# Main_Flight_Computer.net
KiCad netlist of a schematic drawn in EAGLE
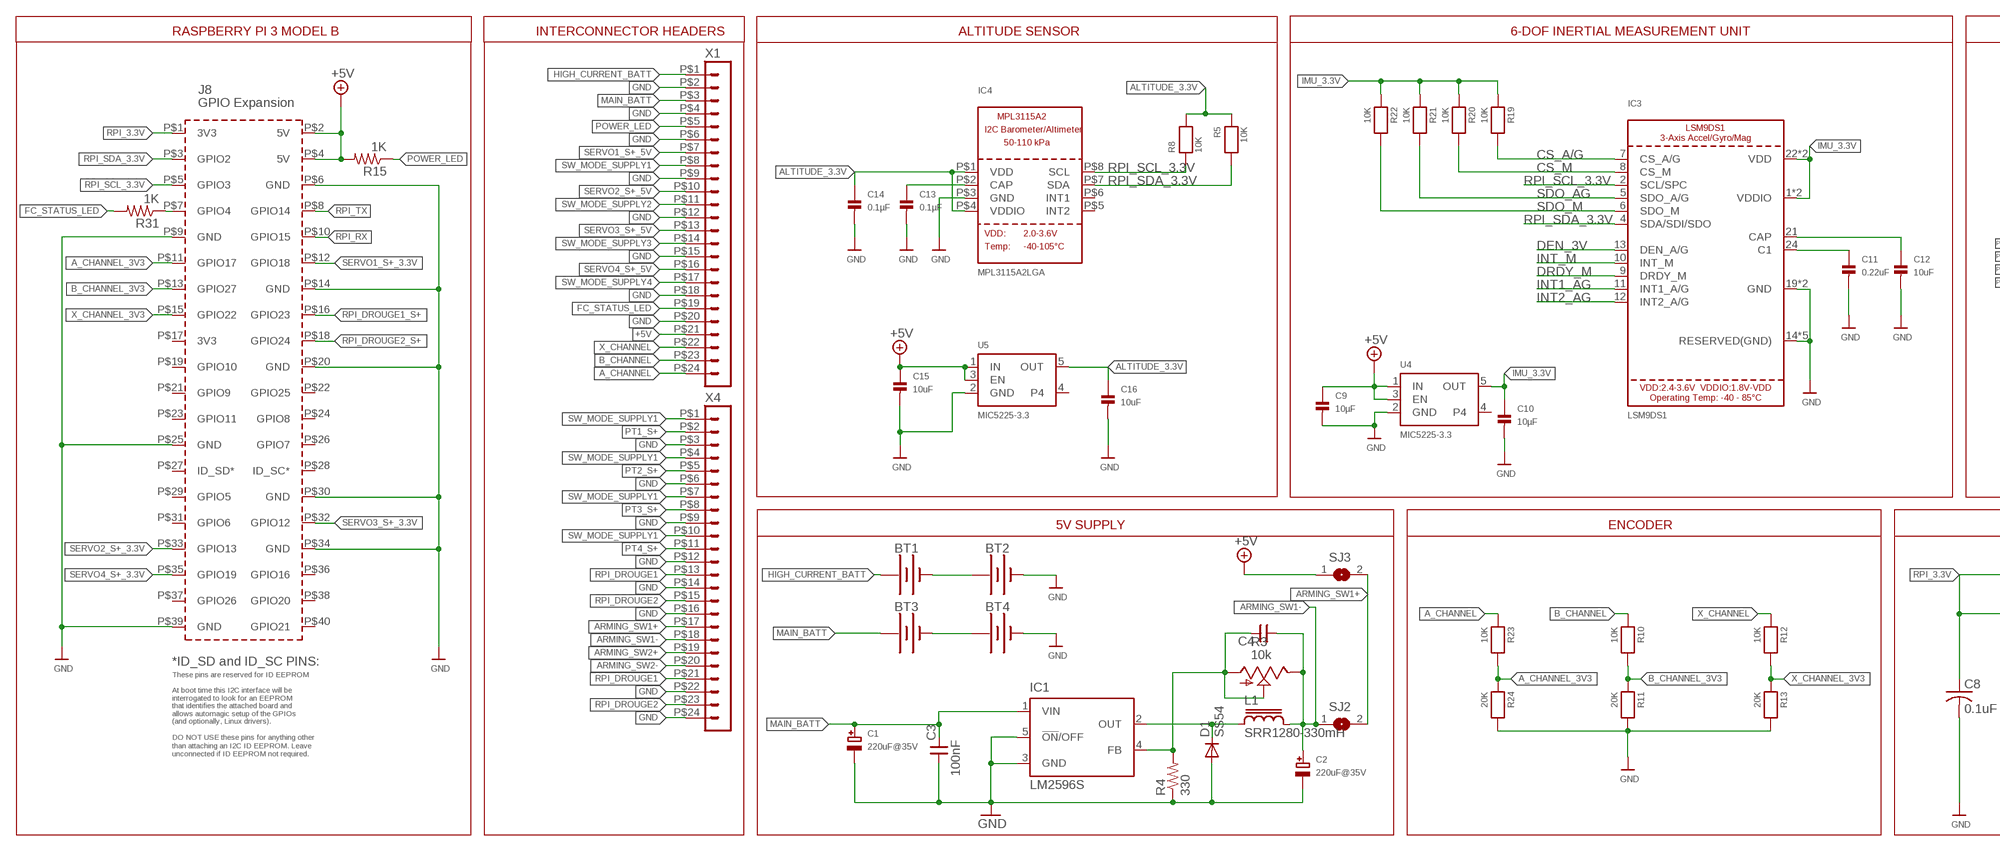
[diagram p0: schematic, sheet 1, part 1 of 2]
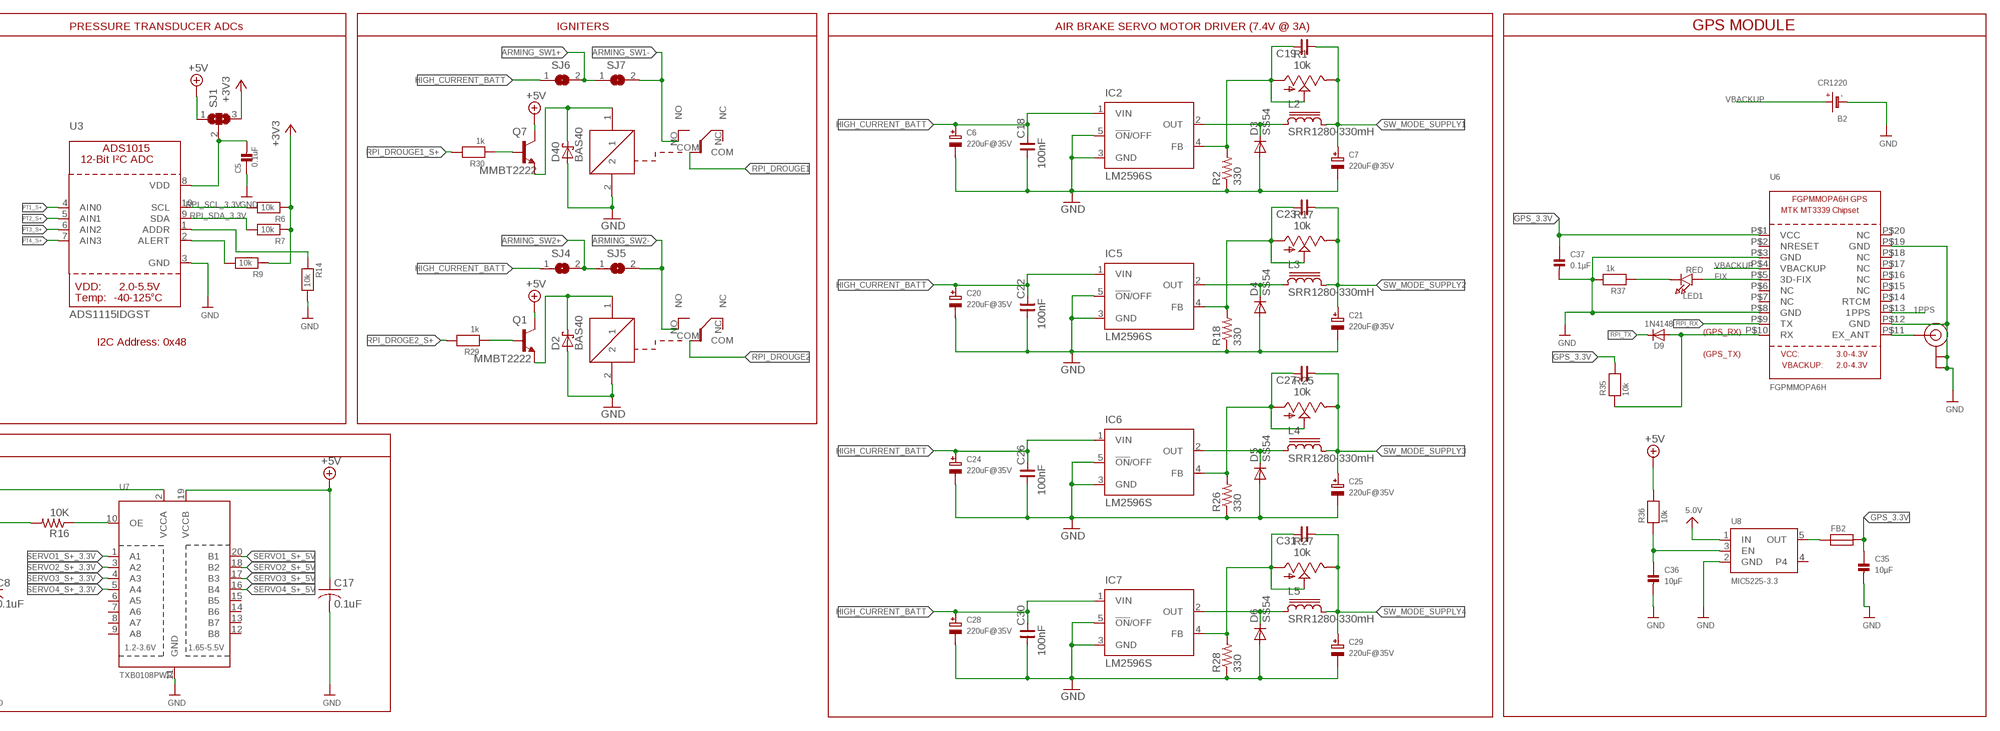
[diagram p1: schematic, sheet 1, part 2 of 2]

(export (version "E")
  (design (tool "Eeschema 10.0.6"))
  (components
    (comp (ref "B2")
      (value "CR1220")
      (footprint "eagle-import:CR1220")
      (libsource (lib "eagle-import") (part "BATTERYCR1220_SMT"))
    )
    (comp (ref "BT1")
      (value "BATTERY-18650")
      (footprint "eagle-import:BATTERY_18650-HOLDER")
      (libsource (lib "eagle-import") (part "BATTERY-18650"))
    )
    (comp (ref "BT2")
      (value "BATTERY-18650")
      (footprint "eagle-import:BATTERY_18650-HOLDER")
      (libsource (lib "eagle-import") (part "BATTERY-18650"))
    )
    (comp (ref "BT3")
      (value "BATTERY-18650")
      (footprint "eagle-import:BATTERY_18650-HOLDER")
      (libsource (lib "eagle-import") (part "BATTERY-18650"))
    )
    (comp (ref "BT4")
      (value "BATTERY-18650")
      (footprint "eagle-import:BATTERY_18650-HOLDER")
      (libsource (lib "eagle-import") (part "BATTERY-18650"))
    )
    (comp (ref "C1")
      (value "220uF@35V")
      (footprint "eagle-import:PANASONIC_D")
      (libsource (lib "eagle-import") (part "CAP_ELECTROLYTICPANASONIC_D"))
    )
    (comp (ref "C2")
      (value "220uF@35V")
      (footprint "eagle-import:PANASONIC_D")
      (libsource (lib "eagle-import") (part "CAP_ELECTROLYTICPANASONIC_D"))
    )
    (comp (ref "C3")
      (value "100nF")
      (footprint "eagle-import:0603")
      (libsource (lib "eagle-import") (part "CNP-0603"))
    )
    (comp (ref "C4")
      (value "CNP-0603")
      (footprint "eagle-import:0603")
      (libsource (lib "eagle-import") (part "CNP-0603"))
    )
    (comp (ref "C5")
      (value "0.1uF")
      (footprint "eagle-import:0805")
      (libsource (lib "eagle-import") (part "CAP_CERAMIC0805"))
    )
    (comp (ref "C6")
      (value "220uF@35V")
      (footprint "eagle-import:PANASONIC_D")
      (libsource (lib "eagle-import") (part "CAP_ELECTROLYTICPANASONIC_D"))
    )
    (comp (ref "C7")
      (value "220uF@35V")
      (footprint "eagle-import:PANASONIC_D")
      (libsource (lib "eagle-import") (part "CAP_ELECTROLYTICPANASONIC_D"))
    )
    (comp (ref "C8")
      (value "0.1uF")
      (footprint "eagle-import:C0805")
      (libsource (lib "eagle-import") (part "C-USC0805"))
    )
    (comp (ref "C9")
      (value "10µF")
      (footprint "eagle-import:0603")
      (libsource (lib "eagle-import") (part "CAP_CERAMIC0603"))
    )
    (comp (ref "C10")
      (value "10µF")
      (footprint "eagle-import:0603")
      (libsource (lib "eagle-import") (part "CAP_CERAMIC0603"))
    )
    (comp (ref "C11")
      (value "0.22uF")
      (footprint "eagle-import:0603")
      (libsource (lib "eagle-import") (part "CAP_CERAMIC0603"))
    )
    (comp (ref "C12")
      (value "10uF")
      (footprint "eagle-import:0603")
      (libsource (lib "eagle-import") (part "CAP_CERAMIC0603"))
    )
    (comp (ref "C13")
      (value "0.1µF")
      (footprint "eagle-import:0603")
      (libsource (lib "eagle-import") (part "CAP_CERAMIC0603"))
    )
    (comp (ref "C14")
      (value "0.1µF")
      (footprint "eagle-import:0603")
      (libsource (lib "eagle-import") (part "CAP_CERAMIC0603"))
    )
    (comp (ref "C15")
      (value "10uF")
      (footprint "eagle-import:0603")
      (libsource (lib "eagle-import") (part "CAP_CERAMIC0603"))
    )
    (comp (ref "C16")
      (value "10uF")
      (footprint "eagle-import:0603")
      (libsource (lib "eagle-import") (part "CAP_CERAMIC0603"))
    )
    (comp (ref "C17")
      (value "0.1uF")
      (footprint "eagle-import:C0805")
      (libsource (lib "eagle-import") (part "C-USC0805"))
    )
    (comp (ref "C18")
      (value "100nF")
      (footprint "eagle-import:0603")
      (libsource (lib "eagle-import") (part "CNP-0603"))
    )
    (comp (ref "C19")
      (value "CNP-0603")
      (footprint "eagle-import:0603")
      (libsource (lib "eagle-import") (part "CNP-0603"))
    )
    (comp (ref "C20")
      (value "220uF@35V")
      (footprint "eagle-import:PANASONIC_D")
      (libsource (lib "eagle-import") (part "CAP_ELECTROLYTICPANASONIC_D"))
    )
    (comp (ref "C21")
      (value "220uF@35V")
      (footprint "eagle-import:PANASONIC_D")
      (libsource (lib "eagle-import") (part "CAP_ELECTROLYTICPANASONIC_D"))
    )
    (comp (ref "C22")
      (value "100nF")
      (footprint "eagle-import:0603")
      (libsource (lib "eagle-import") (part "CNP-0603"))
    )
    (comp (ref "C23")
      (value "CNP-0603")
      (footprint "eagle-import:0603")
      (libsource (lib "eagle-import") (part "CNP-0603"))
    )
    (comp (ref "C24")
      (value "220uF@35V")
      (footprint "eagle-import:PANASONIC_D")
      (libsource (lib "eagle-import") (part "CAP_ELECTROLYTICPANASONIC_D"))
    )
    (comp (ref "C25")
      (value "220uF@35V")
      (footprint "eagle-import:PANASONIC_D")
      (libsource (lib "eagle-import") (part "CAP_ELECTROLYTICPANASONIC_D"))
    )
    (comp (ref "C26")
      (value "100nF")
      (footprint "eagle-import:0603")
      (libsource (lib "eagle-import") (part "CNP-0603"))
    )
    (comp (ref "C27")
      (value "CNP-0603")
      (footprint "eagle-import:0603")
      (libsource (lib "eagle-import") (part "CNP-0603"))
    )
    (comp (ref "C28")
      (value "220uF@35V")
      (footprint "eagle-import:PANASONIC_D")
      (libsource (lib "eagle-import") (part "CAP_ELECTROLYTICPANASONIC_D"))
    )
    (comp (ref "C29")
      (value "220uF@35V")
      (footprint "eagle-import:PANASONIC_D")
      (libsource (lib "eagle-import") (part "CAP_ELECTROLYTICPANASONIC_D"))
    )
    (comp (ref "C30")
      (value "100nF")
      (footprint "eagle-import:0603")
      (libsource (lib "eagle-import") (part "CNP-0603"))
    )
    (comp (ref "C31")
      (value "CNP-0603")
      (footprint "eagle-import:0603")
      (libsource (lib "eagle-import") (part "CNP-0603"))
    )
    (comp (ref "C35")
      (value "10µF")
      (footprint "eagle-import:0603")
      (libsource (lib "eagle-import") (part "CAP_CERAMIC0603"))
    )
    (comp (ref "C36")
      (value "10µF")
      (footprint "eagle-import:0603")
      (libsource (lib "eagle-import") (part "CAP_CERAMIC0603"))
    )
    (comp (ref "C37")
      (value "0.1µF")
      (footprint "eagle-import:0603")
      (libsource (lib "eagle-import") (part "CAP_CERAMIC0603"))
    )
    (comp (ref "D1")
      (value "SS54")
      (footprint "eagle-import:DO214AB")
      (fields (field (name "MF") "Fairchild") (field (name "MPN") "S3G"))
      (libsource (lib "eagle-import") (part "S3G"))
    )
    (comp (ref "D2")
      (value "BAS40")
      (footprint "eagle-import:SOT23")
      (libsource (lib "eagle-import") (part "BAS40"))
    )
    (comp (ref "D3")
      (value "SS54")
      (footprint "eagle-import:DO214AB")
      (fields (field (name "MF") "Fairchild") (field (name "MPN") "S3G"))
      (libsource (lib "eagle-import") (part "S3G"))
    )
    (comp (ref "D4")
      (value "SS54")
      (footprint "eagle-import:DO214AB")
      (fields (field (name "MF") "Fairchild") (field (name "MPN") "S3G"))
      (libsource (lib "eagle-import") (part "S3G"))
    )
    (comp (ref "D5")
      (value "SS54")
      (footprint "eagle-import:DO214AB")
      (fields (field (name "MF") "Fairchild") (field (name "MPN") "S3G"))
      (libsource (lib "eagle-import") (part "S3G"))
    )
    (comp (ref "D6")
      (value "SS54")
      (footprint "eagle-import:DO214AB")
      (fields (field (name "MF") "Fairchild") (field (name "MPN") "S3G"))
      (libsource (lib "eagle-import") (part "S3G"))
    )
    (comp (ref "D9")
      (value "1N4148")
      (footprint "eagle-import:SOD-323")
      (libsource (lib "eagle-import") (part "DIODESOD-323"))
    )
    (comp (ref "D40")
      (value "BAS40")
      (footprint "eagle-import:SOT23")
      (libsource (lib "eagle-import") (part "BAS40"))
    )
    (comp (ref "FB2")
      (value "FERRITE")
      (footprint "eagle-import:0603")
      (libsource (lib "eagle-import") (part "FERRITE"))
    )
    (comp (ref "IC1")
      (value "LM2596S")
      (footprint "eagle-import:TO263-5")
      (fields (field (name "MF") "NATIONAL SEMICONDUCTOR") (field (name "MPN") "LM2596S-ADJ/NOPB"))
      (libsource (lib "eagle-import") (part "LM2596S"))
    )
    (comp (ref "IC2")
      (value "LM2596S")
      (footprint "eagle-import:TO263-5")
      (fields (field (name "MF") "NATIONAL SEMICONDUCTOR") (field (name "MPN") "LM2596S-ADJ/NOPB"))
      (libsource (lib "eagle-import") (part "LM2596S"))
    )
    (comp (ref "IC3")
      (value "LSM9DS1")
      (footprint "eagle-import:LGA24_3.5X3.1MM")
      (libsource (lib "eagle-import") (part "LSM9DS1"))
    )
    (comp (ref "IC4")
      (value "MPL3115A2LGA")
      (footprint "eagle-import:LGA8")
      (libsource (lib "eagle-import") (part "MPL3115A2LGA"))
    )
    (comp (ref "IC5")
      (value "LM2596S")
      (footprint "eagle-import:TO263-5")
      (fields (field (name "MF") "NATIONAL SEMICONDUCTOR") (field (name "MPN") "LM2596S-ADJ/NOPB"))
      (libsource (lib "eagle-import") (part "LM2596S"))
    )
    (comp (ref "IC6")
      (value "LM2596S")
      (footprint "eagle-import:TO263-5")
      (fields (field (name "MF") "NATIONAL SEMICONDUCTOR") (field (name "MPN") "LM2596S-ADJ/NOPB"))
      (libsource (lib "eagle-import") (part "LM2596S"))
    )
    (comp (ref "IC7")
      (value "LM2596S")
      (footprint "eagle-import:TO263-5")
      (fields (field (name "MF") "NATIONAL SEMICONDUCTOR") (field (name "MPN") "LM2596S-ADJ/NOPB"))
      (libsource (lib "eagle-import") (part "LM2596S"))
    )
    (comp (ref "L1")
      (value "SRR1280-330mH")
      (footprint "eagle-import:SRR1280")
      (libsource (lib "eagle-import") (part "SRR1280"))
    )
    (comp (ref "L2")
      (value "SRR1280-330mH")
      (footprint "eagle-import:SRR1280")
      (libsource (lib "eagle-import") (part "SRR1280"))
    )
    (comp (ref "L3")
      (value "SRR1280-330mH")
      (footprint "eagle-import:SRR1280")
      (libsource (lib "eagle-import") (part "SRR1280"))
    )
    (comp (ref "L4")
      (value "SRR1280-330mH")
      (footprint "eagle-import:SRR1280")
      (libsource (lib "eagle-import") (part "SRR1280"))
    )
    (comp (ref "L5")
      (value "SRR1280-330mH")
      (footprint "eagle-import:SRR1280")
      (libsource (lib "eagle-import") (part "SRR1280"))
    )
    (comp (ref "LED1")
      (value "RED")
      (footprint "eagle-import:CHIPLED_0805")
      (libsource (lib "eagle-import") (part "LED0805"))
    )
    (comp (ref "PCB1")
      (value "RPI3")
      (footprint "eagle-import:RPI3")
      (libsource (lib "eagle-import") (part "RPI3"))
    )
    (comp (ref "Q1")
      (value "MMBT2222")
      (footprint "eagle-import:SOT223")
      (libsource (lib "eagle-import") (part "TRANSISTOR_NPN"))
    )
    (comp (ref "Q7")
      (value "MMBT2222")
      (footprint "eagle-import:SOT223")
      (libsource (lib "eagle-import") (part "TRANSISTOR_NPN"))
    )
    (comp (ref "R1")
      (value "10k")
      (footprint "eagle-import:S64W")
      (libsource (lib "eagle-import") (part "TRIM_US-S64W"))
    )
    (comp (ref "R2")
      (value "330")
      (footprint "eagle-import:R0603")
      (libsource (lib "eagle-import") (part "R-US_R0603"))
    )
    (comp (ref "R3")
      (value "10k")
      (footprint "eagle-import:S64W")
      (libsource (lib "eagle-import") (part "TRIM_US-S64W"))
    )
    (comp (ref "R4")
      (value "330")
      (footprint "eagle-import:R0603")
      (libsource (lib "eagle-import") (part "R-US_R0603"))
    )
    (comp (ref "R5")
      (value "10K")
      (footprint "eagle-import:0603")
      (libsource (lib "eagle-import") (part "RESISTOR0603"))
    )
    (comp (ref "R6")
      (value "10k")
      (footprint "eagle-import:0805")
      (libsource (lib "eagle-import") (part "RESISTOR0805"))
    )
    (comp (ref "R7")
      (value "10k")
      (footprint "eagle-import:0805")
      (libsource (lib "eagle-import") (part "RESISTOR0805"))
    )
    (comp (ref "R8")
      (value "10K")
      (footprint "eagle-import:0603")
      (libsource (lib "eagle-import") (part "RESISTOR0603"))
    )
    (comp (ref "R9")
      (value "10k")
      (footprint "eagle-import:0805")
      (libsource (lib "eagle-import") (part "RESISTOR0805"))
    )
    (comp (ref "R10")
      (value "10K")
      (footprint "eagle-import:0603")
      (libsource (lib "eagle-import") (part "RESISTOR0603"))
    )
    (comp (ref "R11")
      (value "20K")
      (footprint "eagle-import:0603")
      (libsource (lib "eagle-import") (part "RESISTOR0603"))
    )
    (comp (ref "R12")
      (value "10K")
      (footprint "eagle-import:0603")
      (libsource (lib "eagle-import") (part "RESISTOR0603"))
    )
    (comp (ref "R13")
      (value "20K")
      (footprint "eagle-import:0603")
      (libsource (lib "eagle-import") (part "RESISTOR0603"))
    )
    (comp (ref "R14")
      (value "10k")
      (footprint "eagle-import:0805")
      (libsource (lib "eagle-import") (part "RESISTOR0805"))
    )
    (comp (ref "R15")
      (value "1K")
      (footprint "eagle-import:R0603")
      (libsource (lib "eagle-import") (part "R-US_R0603"))
    )
    (comp (ref "R16")
      (value "10K")
      (footprint "eagle-import:R0805")
      (libsource (lib "eagle-import") (part "R-US_R0805"))
    )
    (comp (ref "R17")
      (value "10k")
      (footprint "eagle-import:S64W")
      (libsource (lib "eagle-import") (part "TRIM_US-S64W"))
    )
    (comp (ref "R18")
      (value "330")
      (footprint "eagle-import:R0603")
      (libsource (lib "eagle-import") (part "R-US_R0603"))
    )
    (comp (ref "R19")
      (value "10K")
      (footprint "eagle-import:0603")
      (libsource (lib "eagle-import") (part "RESISTOR0603"))
    )
    (comp (ref "R20")
      (value "10K")
      (footprint "eagle-import:0603")
      (libsource (lib "eagle-import") (part "RESISTOR0603"))
    )
    (comp (ref "R21")
      (value "10K")
      (footprint "eagle-import:0603")
      (libsource (lib "eagle-import") (part "RESISTOR0603"))
    )
    (comp (ref "R22")
      (value "10K")
      (footprint "eagle-import:0603")
      (libsource (lib "eagle-import") (part "RESISTOR0603"))
    )
    (comp (ref "R23")
      (value "10K")
      (footprint "eagle-import:0603")
      (libsource (lib "eagle-import") (part "RESISTOR0603"))
    )
    (comp (ref "R24")
      (value "20K")
      (footprint "eagle-import:0603")
      (libsource (lib "eagle-import") (part "RESISTOR0603"))
    )
    (comp (ref "R25")
      (value "10k")
      (footprint "eagle-import:S64W")
      (libsource (lib "eagle-import") (part "TRIM_US-S64W"))
    )
    (comp (ref "R26")
      (value "330")
      (footprint "eagle-import:R0603")
      (libsource (lib "eagle-import") (part "R-US_R0603"))
    )
    (comp (ref "R27")
      (value "10k")
      (footprint "eagle-import:S64W")
      (libsource (lib "eagle-import") (part "TRIM_US-S64W"))
    )
    (comp (ref "R28")
      (value "330")
      (footprint "eagle-import:R0603")
      (libsource (lib "eagle-import") (part "R-US_R0603"))
    )
    (comp (ref "R29")
      (value "1k")
      (footprint "eagle-import:0603")
      (libsource (lib "eagle-import") (part "RESISTOR0603"))
    )
    (comp (ref "R30")
      (value "1k")
      (footprint "eagle-import:0603")
      (libsource (lib "eagle-import") (part "RESISTOR0603"))
    )
    (comp (ref "R31")
      (value "1K")
      (footprint "eagle-import:R0603")
      (libsource (lib "eagle-import") (part "R-US_R0603"))
    )
    (comp (ref "R35")
      (value "10k")
      (footprint "eagle-import:0603")
      (libsource (lib "eagle-import") (part "RESISTOR0603"))
    )
    (comp (ref "R36")
      (value "10k")
      (footprint "eagle-import:0603")
      (libsource (lib "eagle-import") (part "RESISTOR0603"))
    )
    (comp (ref "R37")
      (value "1k")
      (footprint "eagle-import:0603")
      (libsource (lib "eagle-import") (part "RESISTOR0603"))
    )
    (comp (ref "SJ1")
      (value "SJ2W")
      (footprint "eagle-import:SJ_2")
      (libsource (lib "eagle-import") (part "SJ2W"))
    )
    (comp (ref "SJ2") (value "SJ") (footprint "eagle-import:SJ") (libsource (lib "eagle-import") (part "SJ")))
    (comp (ref "SJ3") (value "SJ") (footprint "eagle-import:SJ") (libsource (lib "eagle-import") (part "SJ")))
    (comp (ref "SJ4") (value "SJ") (footprint "eagle-import:SJ") (libsource (lib "eagle-import") (part "SJ")))
    (comp (ref "SJ5") (value "SJ") (footprint "eagle-import:SJ") (libsource (lib "eagle-import") (part "SJ")))
    (comp (ref "SJ6")
      (value "SJ")
      (footprint "eagle-import:SJ")
      (libsource (lib "eagle-import") (part "jumper_252_SJ"))
    )
    (comp (ref "SJ7") (value "SJ") (footprint "eagle-import:SJ") (libsource (lib "eagle-import") (part "SJ")))
    (comp (ref "U$2")
      (value "U.FL")
      (footprint "eagle-import:U.FL")
      (libsource (lib "eagle-import") (part "U.FL"))
    )
    (comp (ref "U$11")
      (value "RW-SH")
      (footprint "eagle-import:RW-SH")
      (libsource (lib "eagle-import") (part "RW-SH"))
    )
    (comp (ref "U$13")
      (value "RW-SH")
      (footprint "eagle-import:RW-SH")
      (libsource (lib "eagle-import") (part "RW-SH"))
    )
    (comp (ref "U3")
      (value "ADS1115IDGST")
      (footprint "eagle-import:MSOP10")
      (libsource (lib "eagle-import") (part "ADC_ADS1015"))
    )
    (comp (ref "U4")
      (value "MIC5225-3.3")
      (footprint "eagle-import:SOT23-5")
      (libsource (lib "eagle-import") (part "VREG_SOT23-5"))
    )
    (comp (ref "U5")
      (value "MIC5225-3.3")
      (footprint "eagle-import:SOT23-5")
      (libsource (lib "eagle-import") (part "VREG_SOT23-5"))
    )
    (comp (ref "U6")
      (value "FGPMMOPA6H")
      (footprint "eagle-import:FGPMMOPA6H")
      (libsource (lib "eagle-import") (part "GPS_FGPMMOPA6H"))
    )
    (comp (ref "U7")
      (value "TXB0108PWR")
      (footprint "eagle-import:TSSOP20")
      (libsource (lib "eagle-import") (part "TXB0108PWR"))
    )
    (comp (ref "U8")
      (value "MIC5225-3.3")
      (footprint "eagle-import:SOT23-5")
      (libsource (lib "eagle-import") (part "VREG_SOT23-5"))
    )
    (comp (ref "X1")
      (value "HEADER_POS24_44914-2401")
      (footprint "eagle-import:44914-2401")
      (libsource (lib "eagle-import") (part "HEADER_POS24_?44914-2401"))
    )
    (comp (ref "X4")
      (value "HEADER_POS24_44914-2401")
      (footprint "eagle-import:44914-2401")
      (libsource (lib "eagle-import") (part "HEADER_POS24_?44914-2401"))
    )
  )
  (nets
    (net (code "1") (name "+3V3") (class "Default")
      (node (ref "R6") (pin "1") (pinfunction "1_1") (pintype "passive"))
      (node (ref "R7") (pin "1") (pinfunction "1_1") (pintype "passive"))
      (node (ref "R9") (pin "1") (pinfunction "1_1") (pintype "passive"))
      (node (ref "SJ1") (pin "3") (pinfunction "3_3") (pintype "passive"))
    )
    (net (code "2") (name "+5V") (class "Default")
      (node (ref "C15") (pin "1") (pinfunction "P$1_1") (pintype "passive"))
      (node (ref "C17") (pin "1") (pinfunction "1_1") (pintype "passive"))
      (node (ref "C9") (pin "1") (pinfunction "P$1_1") (pintype "passive"))
      (node (ref "PCB1") (pin "P$2") (pinfunction "5V_P$2") (pintype "bidirectional"))
      (node (ref "PCB1") (pin "P$4") (pinfunction "5V_P$4") (pintype "bidirectional"))
      (node (ref "Q1") (pin "2") (pinfunction "C_2") (pintype "passive"))
      (node (ref "Q7") (pin "2") (pinfunction "C_2") (pintype "passive"))
      (node (ref "R15") (pin "2") (pinfunction "2_2") (pintype "passive"))
      (node (ref "R36") (pin "2") (pinfunction "2_2") (pintype "passive"))
      (node (ref "SJ1") (pin "1") (pinfunction "1_1") (pintype "passive"))
      (node (ref "SJ3") (pin "1") (pinfunction "1_1") (pintype "passive"))
      (node (ref "U4") (pin "1") (pinfunction "IN_1") (pintype "power_in"))
      (node (ref "U4") (pin "3") (pinfunction "EN_3") (pintype "input"))
      (node (ref "U5") (pin "1") (pinfunction "IN_1") (pintype "power_in"))
      (node (ref "U5") (pin "3") (pinfunction "EN_3") (pintype "input"))
      (node (ref "U7") (pin "19") (pinfunction "VCCB_19") (pintype "bidirectional"))
      (node (ref "X1") (pin "P$21") (pinfunction "21_P$21") (pintype "passive"))
    )
    (net (code "3") (name "/1PPS") (class "Default")
      (node (ref "U6") (pin "P$13") (pinfunction "1PPS_P$13") (pintype "bidirectional"))
    )
    (net (code "4") (name "/CS_A{slash}G") (class "Default")
      (node (ref "IC3") (pin "7") (pinfunction "CS_A/G_7") (pintype "bidirectional"))
      (node (ref "R19") (pin "2") (pinfunction "2_2") (pintype "passive"))
    )
    (net (code "5") (name "/CS_M") (class "Default")
      (node (ref "IC3") (pin "8") (pinfunction "CS_M_8") (pintype "bidirectional"))
      (node (ref "R20") (pin "2") (pinfunction "2_2") (pintype "passive"))
    )
    (net (code "6") (name "/DEN_3V") (class "Default")
      (node (ref "IC3") (pin "13") (pinfunction "DEN_A/G_13") (pintype "bidirectional"))
    )
    (net (code "7") (name "/DRDY_M") (class "Default")
      (node (ref "IC3") (pin "9") (pinfunction "DRDY_M_9") (pintype "bidirectional"))
    )
    (net (code "8") (name "/FIX") (class "Default")
      (node (ref "LED1") (pin "A") (pinfunction "A_A") (pintype "passive"))
      (node (ref "U6") (pin "P$5") (pinfunction "3D-FIX_P$5") (pintype "bidirectional"))
    )
    (net (code "9") (name "/INT1_AG") (class "Default")
      (node (ref "IC3") (pin "11") (pinfunction "INT1_A/G_11") (pintype "bidirectional"))
    )
    (net (code "10") (name "/INT2_AG") (class "Default")
      (node (ref "IC3") (pin "12") (pinfunction "INT2_A/G_12") (pintype "bidirectional"))
    )
    (net (code "11") (name "/INT_M") (class "Default")
      (node (ref "IC3") (pin "10") (pinfunction "INT_M_10") (pintype "bidirectional"))
    )
    (net (code "12") (name "/SDO_AG") (class "Default")
      (node (ref "IC3") (pin "5") (pinfunction "SDO_A/G_5") (pintype "bidirectional"))
      (node (ref "R21") (pin "2") (pinfunction "2_2") (pintype "passive"))
    )
    (net (code "13") (name "/SDO_M") (class "Default")
      (node (ref "IC3") (pin "6") (pinfunction "SDO_M_6") (pintype "bidirectional"))
      (node (ref "R22") (pin "2") (pinfunction "2_2") (pintype "passive"))
    )
    (net (code "14") (name "/VBACKUP") (class "Default")
      (node (ref "B2") (pin "+$1") (pinfunction "+_+$1") (pintype "passive"))
      (node (ref "B2") (pin "+$2") (pinfunction "+_+$2") (pintype "passive"))
      (node (ref "U6") (pin "P$4") (pinfunction "VBACKUP_P$4") (pintype "bidirectional"))
    )
    (net (code "15") (name "5.0V") (class "Default")
      (node (ref "U8") (pin "1") (pinfunction "IN_1") (pintype "power_in"))
    )
    (net (code "16") (name "ALTITUDE_3.3V") (class "Default")
      (node (ref "C14") (pin "1") (pinfunction "P$1_1") (pintype "passive"))
      (node (ref "C16") (pin "1") (pinfunction "P$1_1") (pintype "passive"))
      (node (ref "IC4") (pin "P$1") (pinfunction "VDD_P$1") (pintype "power_in"))
      (node (ref "IC4") (pin "P$4") (pinfunction "VDDIO_P$4") (pintype "power_in"))
      (node (ref "R5") (pin "1") (pinfunction "1_1") (pintype "passive"))
      (node (ref "R8") (pin "2") (pinfunction "2_2") (pintype "passive"))
      (node (ref "U5") (pin "5") (pinfunction "OUT_5") (pintype "power_in"))
    )
    (net (code "17") (name "ARMING_SW1+") (class "Default")
      (node (ref "SJ2") (pin "2") (pinfunction "2_2") (pintype "passive"))
      (node (ref "SJ3") (pin "2") (pinfunction "2_2") (pintype "passive"))
      (node (ref "SJ6") (pin "2") (pinfunction "2_2") (pintype "passive"))
      (node (ref "SJ7") (pin "1") (pinfunction "1_1") (pintype "passive"))
      (node (ref "X4") (pin "P$17") (pinfunction "17_P$17") (pintype "passive"))
    )
    (net (code "18") (name "ARMING_SW1-") (class "Default")
      (node (ref "C2") (pin "+") (pinfunction "+_+") (pintype "passive"))
      (node (ref "C4") (pin "1") (pinfunction "1_1") (pintype "passive"))
      (node (ref "L1") (pin "2") (pinfunction "2_2") (pintype "passive"))
      (node (ref "R3") (pin "E") (pinfunction "E_E") (pintype "passive"))
      (node (ref "SJ2") (pin "1") (pinfunction "1_1") (pintype "passive"))
      (node (ref "SJ7") (pin "2") (pinfunction "2_2") (pintype "passive"))
      (node (ref "U$11") (pin "NO") (pinfunction "NO_NO") (pintype "bidirectional"))
      (node (ref "X4") (pin "P$18") (pinfunction "18_P$18") (pintype "passive"))
    )
    (net (code "19") (name "ARMING_SW2+") (class "Default")
      (node (ref "SJ4") (pin "2") (pinfunction "2_2") (pintype "passive"))
      (node (ref "SJ5") (pin "1") (pinfunction "1_1") (pintype "passive"))
      (node (ref "X4") (pin "P$19") (pinfunction "19_P$19") (pintype "passive"))
    )
    (net (code "20") (name "ARMING_SW2-") (class "Default")
      (node (ref "SJ5") (pin "2") (pinfunction "2_2") (pintype "passive"))
      (node (ref "U$13") (pin "NO") (pinfunction "NO_NO") (pintype "bidirectional"))
      (node (ref "X4") (pin "P$20") (pinfunction "20_P$20") (pintype "passive"))
    )
    (net (code "21") (name "A_CHANNEL") (class "Default")
      (node (ref "R23") (pin "1") (pinfunction "1_1") (pintype "passive"))
      (node (ref "X1") (pin "P$24") (pinfunction "24_P$24") (pintype "passive"))
    )
    (net (code "22") (name "A_CHANNEL_3V3") (class "Default")
      (node (ref "PCB1") (pin "P$11") (pinfunction "GPIO17_P$11") (pintype "bidirectional"))
      (node (ref "R23") (pin "2") (pinfunction "2_2") (pintype "passive"))
      (node (ref "R24") (pin "1") (pinfunction "1_1") (pintype "passive"))
    )
    (net (code "23") (name "B_CHANNEL") (class "Default")
      (node (ref "R10") (pin "1") (pinfunction "1_1") (pintype "passive"))
      (node (ref "X1") (pin "P$23") (pinfunction "23_P$23") (pintype "passive"))
    )
    (net (code "24") (name "B_CHANNEL_3V3") (class "Default")
      (node (ref "PCB1") (pin "P$13") (pinfunction "GPIO27_P$13") (pintype "bidirectional"))
      (node (ref "R10") (pin "2") (pinfunction "2_2") (pintype "passive"))
      (node (ref "R11") (pin "1") (pinfunction "1_1") (pintype "passive"))
    )
    (net (code "25") (name "FC_STATUS_LED") (class "Default")
      (node (ref "R31") (pin "2") (pinfunction "2_2") (pintype "passive"))
      (node (ref "X1") (pin "P$19") (pinfunction "19_P$19") (pintype "passive"))
    )
    (net (code "26") (name "GND") (class "Default")
      (node (ref "B2") (pin "-") (pinfunction "-_-") (pintype "passive"))
      (node (ref "BT2") (pin "GND@1") (pinfunction "-_GND@1") (pintype "power_in"))
      (node (ref "BT4") (pin "GND@1") (pinfunction "-_GND@1") (pintype "power_in"))
      (node (ref "C1") (pin "-") (pinfunction "-_-") (pintype "passive"))
      (node (ref "C10") (pin "2") (pinfunction "P$2_2") (pintype "passive"))
      (node (ref "C11") (pin "2") (pinfunction "P$2_2") (pintype "passive"))
      (node (ref "C12") (pin "2") (pinfunction "P$2_2") (pintype "passive"))
      (node (ref "C13") (pin "2") (pinfunction "P$2_2") (pintype "passive"))
      (node (ref "C14") (pin "2") (pinfunction "P$2_2") (pintype "passive"))
      (node (ref "C15") (pin "2") (pinfunction "P$2_2") (pintype "passive"))
      (node (ref "C16") (pin "2") (pinfunction "P$2_2") (pintype "passive"))
      (node (ref "C17") (pin "2") (pinfunction "2_2") (pintype "passive"))
      (node (ref "C18") (pin "1") (pinfunction "1_1") (pintype "passive"))
      (node (ref "C2") (pin "-") (pinfunction "-_-") (pintype "passive"))
      (node (ref "C20") (pin "-") (pinfunction "-_-") (pintype "passive"))
      (node (ref "C21") (pin "-") (pinfunction "-_-") (pintype "passive"))
      (node (ref "C22") (pin "1") (pinfunction "1_1") (pintype "passive"))
      (node (ref "C24") (pin "-") (pinfunction "-_-") (pintype "passive"))
      (node (ref "C25") (pin "-") (pinfunction "-_-") (pintype "passive"))
      (node (ref "C26") (pin "1") (pinfunction "1_1") (pintype "passive"))
      (node (ref "C28") (pin "-") (pinfunction "-_-") (pintype "passive"))
      (node (ref "C29") (pin "-") (pinfunction "-_-") (pintype "passive"))
      (node (ref "C3") (pin "1") (pinfunction "1_1") (pintype "passive"))
      (node (ref "C30") (pin "1") (pinfunction "1_1") (pintype "passive"))
      (node (ref "C35") (pin "2") (pinfunction "P$2_2") (pintype "passive"))
      (node (ref "C36") (pin "2") (pinfunction "P$2_2") (pintype "passive"))
      (node (ref "C37") (pin "2") (pinfunction "P$2_2") (pintype "passive"))
      (node (ref "C5") (pin "1") (pinfunction "P$1_1") (pintype "passive"))
      (node (ref "C6") (pin "-") (pinfunction "-_-") (pintype "passive"))
      (node (ref "C7") (pin "-") (pinfunction "-_-") (pintype "passive"))
      (node (ref "C8") (pin "2") (pinfunction "2_2") (pintype "passive"))
      (node (ref "C9") (pin "2") (pinfunction "P$2_2") (pintype "passive"))
      (node (ref "D1") (pin "A") (pinfunction "A_A") (pintype "passive"))
      (node (ref "D2") (pin "1") (pinfunction "A_1") (pintype "passive"))
      (node (ref "D3") (pin "A") (pinfunction "A_A") (pintype "passive"))
      (node (ref "D4") (pin "A") (pinfunction "A_A") (pintype "passive"))
      (node (ref "D40") (pin "1") (pinfunction "A_1") (pintype "passive"))
      (node (ref "D5") (pin "A") (pinfunction "A_A") (pintype "passive"))
      (node (ref "D6") (pin "A") (pinfunction "A_A") (pintype "passive"))
      (node (ref "IC1") (pin "3") (pinfunction "GND_3") (pintype "power_in"))
      (node (ref "IC1") (pin "5") (pinfunction "~{ON}/OFF_5") (pintype "input"))
      (node (ref "IC2") (pin "3") (pinfunction "GND_3") (pintype "power_in"))
      (node (ref "IC2") (pin "5") (pinfunction "~{ON}/OFF_5") (pintype "input"))
      (node (ref "IC3") (pin "14") (pinfunction "RESERVED(GND)_14") (pintype "power_in"))
      (node (ref "IC3") (pin "15") (pinfunction "RESERVED(GND)_15") (pintype "power_in"))
      (node (ref "IC3") (pin "16") (pinfunction "RESERVED(GND)_16") (pintype "power_in"))
      (node (ref "IC3") (pin "17") (pinfunction "RESERVED(GND)_17") (pintype "power_in"))
      (node (ref "IC3") (pin "18") (pinfunction "RESERVED(GND)_18") (pintype "power_in"))
      (node (ref "IC3") (pin "19") (pinfunction "GND_19") (pintype "power_in"))
      (node (ref "IC3") (pin "20") (pinfunction "GND_20") (pintype "power_in"))
      (node (ref "IC4") (pin "P$3") (pinfunction "GND_P$3") (pintype "power_in"))
      (node (ref "IC5") (pin "3") (pinfunction "GND_3") (pintype "power_in"))
      (node (ref "IC5") (pin "5") (pinfunction "~{ON}/OFF_5") (pintype "input"))
      (node (ref "IC6") (pin "3") (pinfunction "GND_3") (pintype "power_in"))
      (node (ref "IC6") (pin "5") (pinfunction "~{ON}/OFF_5") (pintype "input"))
      (node (ref "IC7") (pin "3") (pinfunction "GND_3") (pintype "power_in"))
      (node (ref "IC7") (pin "5") (pinfunction "~{ON}/OFF_5") (pintype "input"))
      (node (ref "PCB1") (pin "P$14") (pinfunction "GND_P$14") (pintype "bidirectional"))
      (node (ref "PCB1") (pin "P$20") (pinfunction "GND_P$20") (pintype "bidirectional"))
      (node (ref "PCB1") (pin "P$25") (pinfunction "GND_P$25") (pintype "bidirectional"))
      (node (ref "PCB1") (pin "P$30") (pinfunction "GND_P$30") (pintype "bidirectional"))
      (node (ref "PCB1") (pin "P$34") (pinfunction "GND_P$34") (pintype "bidirectional"))
      (node (ref "PCB1") (pin "P$39") (pinfunction "GND_P$39") (pintype "bidirectional"))
      (node (ref "PCB1") (pin "P$6") (pinfunction "GND_P$6") (pintype "bidirectional"))
      (node (ref "PCB1") (pin "P$9") (pinfunction "GND_P$9") (pintype "bidirectional"))
      (node (ref "R11") (pin "2") (pinfunction "2_2") (pintype "passive"))
      (node (ref "R13") (pin "2") (pinfunction "2_2") (pintype "passive"))
      (node (ref "R14") (pin "2") (pinfunction "2_2") (pintype "passive"))
      (node (ref "R18") (pin "1") (pinfunction "1_1") (pintype "passive"))
      (node (ref "R2") (pin "1") (pinfunction "1_1") (pintype "passive"))
      (node (ref "R24") (pin "2") (pinfunction "2_2") (pintype "passive"))
      (node (ref "R26") (pin "1") (pinfunction "1_1") (pintype "passive"))
      (node (ref "R28") (pin "1") (pinfunction "1_1") (pintype "passive"))
      (node (ref "R37") (pin "2") (pinfunction "2_2") (pintype "passive"))
      (node (ref "R4") (pin "1") (pinfunction "1_1") (pintype "passive"))
      (node (ref "U$11") (pin "2") (pinfunction "2_2") (pintype "bidirectional"))
      (node (ref "U$13") (pin "2") (pinfunction "2_2") (pintype "bidirectional"))
      (node (ref "U$2") (pin "P$1") (pinfunction "GND_P$1") (pintype "bidirectional"))
      (node (ref "U$2") (pin "P$2") (pinfunction "GND_P$2") (pintype "bidirectional"))
      (node (ref "U3") (pin "3") (pinfunction "GND_3") (pintype "bidirectional"))
      (node (ref "U4") (pin "2") (pinfunction "GND_2") (pintype "power_in"))
      (node (ref "U5") (pin "2") (pinfunction "GND_2") (pintype "power_in"))
      (node (ref "U6") (pin "P$12") (pinfunction "GND_P$12") (pintype "bidirectional"))
      (node (ref "U6") (pin "P$19") (pinfunction "GND_P$19") (pintype "bidirectional"))
      (node (ref "U6") (pin "P$3") (pinfunction "GND_P$3") (pintype "bidirectional"))
      (node (ref "U6") (pin "P$8") (pinfunction "GND_P$8") (pintype "bidirectional"))
      (node (ref "U7") (pin "11") (pinfunction "GND_11") (pintype "bidirectional"))
      (node (ref "U8") (pin "2") (pinfunction "GND_2") (pintype "power_in"))
      (node (ref "X1") (pin "P$12") (pinfunction "12_P$12") (pintype "passive"))
      (node (ref "X1") (pin "P$15") (pinfunction "15_P$15") (pintype "passive"))
      (node (ref "X1") (pin "P$18") (pinfunction "18_P$18") (pintype "passive"))
      (node (ref "X1") (pin "P$2") (pinfunction "2_P$2") (pintype "passive"))
      (node (ref "X1") (pin "P$20") (pinfunction "20_P$20") (pintype "passive"))
      (node (ref "X1") (pin "P$4") (pinfunction "4_P$4") (pintype "passive"))
      (node (ref "X1") (pin "P$6") (pinfunction "6_P$6") (pintype "passive"))
      (node (ref "X1") (pin "P$9") (pinfunction "9_P$9") (pintype "passive"))
      (node (ref "X4") (pin "P$12") (pinfunction "12_P$12") (pintype "passive"))
      (node (ref "X4") (pin "P$14") (pinfunction "14_P$14") (pintype "passive"))
      (node (ref "X4") (pin "P$16") (pinfunction "16_P$16") (pintype "passive"))
      (node (ref "X4") (pin "P$22") (pinfunction "22_P$22") (pintype "passive"))
      (node (ref "X4") (pin "P$24") (pinfunction "24_P$24") (pintype "passive"))
      (node (ref "X4") (pin "P$3") (pinfunction "3_P$3") (pintype "passive"))
      (node (ref "X4") (pin "P$6") (pinfunction "6_P$6") (pintype "passive"))
      (node (ref "X4") (pin "P$9") (pinfunction "9_P$9") (pintype "passive"))
    )
    (net (code "27") (name "GPS_3.3V") (class "Default")
      (node (ref "C35") (pin "1") (pinfunction "P$1_1") (pintype "passive"))
      (node (ref "C37") (pin "1") (pinfunction "P$1_1") (pintype "passive"))
      (node (ref "FB2") (pin "2") (pinfunction "P$2_2") (pintype "bidirectional"))
      (node (ref "R35") (pin "2") (pinfunction "2_2") (pintype "passive"))
      (node (ref "U6") (pin "P$1") (pinfunction "VCC_P$1") (pintype "bidirectional"))
    )
    (net (code "28") (name "HIGH_CURRENT_BATT") (class "Default")
      (node (ref "BT1") (pin "PWR@1") (pinfunction "+_PWR@1") (pintype "power_in"))
      (node (ref "C18") (pin "2") (pinfunction "2_2") (pintype "passive"))
      (node (ref "C20") (pin "+") (pinfunction "+_+") (pintype "passive"))
      (node (ref "C22") (pin "2") (pinfunction "2_2") (pintype "passive"))
      (node (ref "C24") (pin "+") (pinfunction "+_+") (pintype "passive"))
      (node (ref "C26") (pin "2") (pinfunction "2_2") (pintype "passive"))
      (node (ref "C28") (pin "+") (pinfunction "+_+") (pintype "passive"))
      (node (ref "C30") (pin "2") (pinfunction "2_2") (pintype "passive"))
      (node (ref "C6") (pin "+") (pinfunction "+_+") (pintype "passive"))
      (node (ref "IC2") (pin "1") (pinfunction "VIN_1") (pintype "input"))
      (node (ref "IC5") (pin "1") (pinfunction "VIN_1") (pintype "input"))
      (node (ref "IC6") (pin "1") (pinfunction "VIN_1") (pintype "input"))
      (node (ref "IC7") (pin "1") (pinfunction "VIN_1") (pintype "input"))
      (node (ref "SJ4") (pin "1") (pinfunction "1_1") (pintype "passive"))
      (node (ref "SJ6") (pin "1") (pinfunction "1_1") (pintype "passive"))
      (node (ref "X1") (pin "P$1") (pinfunction "1_P$1") (pintype "passive"))
    )
    (net (code "29") (name "IMU_3.3V") (class "Default")
      (node (ref "C10") (pin "1") (pinfunction "P$1_1") (pintype "passive"))
      (node (ref "IC3") (pin "1") (pinfunction "VDDIO_1") (pintype "power_in"))
      (node (ref "IC3") (pin "22") (pinfunction "VDD_22") (pintype "power_in"))
      (node (ref "IC3") (pin "23") (pinfunction "VDD_23") (pintype "power_in"))
      (node (ref "IC3") (pin "3") (pinfunction "VDDIO_3") (pintype "power_in"))
      (node (ref "R19") (pin "1") (pinfunction "1_1") (pintype "passive"))
      (node (ref "R20") (pin "1") (pinfunction "1_1") (pintype "passive"))
      (node (ref "R21") (pin "1") (pinfunction "1_1") (pintype "passive"))
      (node (ref "R22") (pin "1") (pinfunction "1_1") (pintype "passive"))
      (node (ref "U4") (pin "5") (pinfunction "OUT_5") (pintype "power_in"))
    )
    (net (code "30") (name "MAIN_BATT") (class "Default")
      (node (ref "BT3") (pin "PWR@1") (pinfunction "+_PWR@1") (pintype "power_in"))
      (node (ref "C1") (pin "+") (pinfunction "+_+") (pintype "passive"))
      (node (ref "C3") (pin "2") (pinfunction "2_2") (pintype "passive"))
      (node (ref "IC1") (pin "1") (pinfunction "VIN_1") (pintype "input"))
      (node (ref "X1") (pin "P$3") (pinfunction "3_P$3") (pintype "passive"))
    )
    (net (code "31") (name "Net-(BT1--)") (class "Default")
      (node (ref "BT1") (pin "GND@1") (pinfunction "-_GND@1") (pintype "power_in"))
      (node (ref "BT2") (pin "PWR@1") (pinfunction "+_PWR@1") (pintype "power_in"))
    )
    (net (code "32") (name "Net-(BT3--)") (class "Default")
      (node (ref "BT3") (pin "GND@1") (pinfunction "-_GND@1") (pintype "power_in"))
      (node (ref "BT4") (pin "PWR@1") (pinfunction "+_PWR@1") (pintype "power_in"))
    )
    (net (code "33") (name "Net-(C5-P$2)") (class "Default")
      (node (ref "C5") (pin "2") (pinfunction "P$2_2") (pintype "passive"))
      (node (ref "SJ1") (pin "2") (pinfunction "2_2") (pintype "passive"))
      (node (ref "U3") (pin "8") (pinfunction "VDD_8") (pintype "bidirectional"))
    )
    (net (code "34") (name "Net-(C11-P$1)") (class "Default")
      (node (ref "C11") (pin "1") (pinfunction "P$1_1") (pintype "passive"))
      (node (ref "IC3") (pin "24") (pinfunction "C1_24") (pintype "bidirectional"))
    )
    (net (code "35") (name "Net-(C12-P$1)") (class "Default")
      (node (ref "C12") (pin "1") (pinfunction "P$1_1") (pintype "passive"))
      (node (ref "IC3") (pin "21") (pinfunction "CAP_21") (pintype "bidirectional"))
    )
    (net (code "36") (name "Net-(C13-P$1)") (class "Default")
      (node (ref "C13") (pin "1") (pinfunction "P$1_1") (pintype "passive"))
      (node (ref "IC4") (pin "P$2") (pinfunction "CAP_P$2") (pintype "passive"))
    )
    (net (code "37") (name "Net-(C36-P$1)") (class "Default")
      (node (ref "C36") (pin "1") (pinfunction "P$1_1") (pintype "passive"))
      (node (ref "R36") (pin "1") (pinfunction "1_1") (pintype "passive"))
      (node (ref "U8") (pin "3") (pinfunction "EN_3") (pintype "input"))
    )
    (net (code "38") (name "Net-(D2-C)") (class "Default")
      (node (ref "D2") (pin "3") (pinfunction "C_3") (pintype "passive"))
      (node (ref "Q1") (pin "3") (pinfunction "E_3") (pintype "passive"))
      (node (ref "U$13") (pin "1") (pinfunction "1_1") (pintype "bidirectional"))
    )
    (net (code "39") (name "Net-(D40-C)") (class "Default")
      (node (ref "D40") (pin "3") (pinfunction "C_3") (pintype "passive"))
      (node (ref "Q7") (pin "3") (pinfunction "E_3") (pintype "passive"))
      (node (ref "U$11") (pin "1") (pinfunction "1_1") (pintype "bidirectional"))
    )
    (net (code "40") (name "Net-(FB2-P$1)") (class "Default")
      (node (ref "FB2") (pin "1") (pinfunction "P$1_1") (pintype "bidirectional"))
      (node (ref "U8") (pin "5") (pinfunction "OUT_5") (pintype "power_in"))
    )
    (net (code "41") (name "Net-(IC1-FB)") (class "Default")
      (node (ref "C4") (pin "2") (pinfunction "2_2") (pintype "passive"))
      (node (ref "IC1") (pin "4") (pinfunction "FB_4") (pintype "input"))
      (node (ref "R3") (pin "A") (pinfunction "A_A") (pintype "passive"))
      (node (ref "R3") (pin "S") (pinfunction "S_S") (pintype "passive"))
      (node (ref "R4") (pin "2") (pinfunction "2_2") (pintype "passive"))
    )
    (net (code "42") (name "Net-(IC1-OUT)") (class "Default")
      (node (ref "D1") (pin "C") (pinfunction "C_C") (pintype "passive"))
      (node (ref "IC1") (pin "2") (pinfunction "OUT_2") (pintype "output"))
      (node (ref "L1") (pin "1") (pinfunction "1_1") (pintype "passive"))
    )
    (net (code "43") (name "Net-(IC2-FB)") (class "Default")
      (node (ref "C19") (pin "2") (pinfunction "2_2") (pintype "passive"))
      (node (ref "IC2") (pin "4") (pinfunction "FB_4") (pintype "input"))
      (node (ref "R1") (pin "A") (pinfunction "A_A") (pintype "passive"))
      (node (ref "R1") (pin "S") (pinfunction "S_S") (pintype "passive"))
      (node (ref "R2") (pin "2") (pinfunction "2_2") (pintype "passive"))
    )
    (net (code "44") (name "Net-(IC2-OUT)") (class "Default")
      (node (ref "D3") (pin "C") (pinfunction "C_C") (pintype "passive"))
      (node (ref "IC2") (pin "2") (pinfunction "OUT_2") (pintype "output"))
      (node (ref "L2") (pin "1") (pinfunction "1_1") (pintype "passive"))
    )
    (net (code "45") (name "Net-(IC5-FB)") (class "Default")
      (node (ref "C23") (pin "2") (pinfunction "2_2") (pintype "passive"))
      (node (ref "IC5") (pin "4") (pinfunction "FB_4") (pintype "input"))
      (node (ref "R17") (pin "A") (pinfunction "A_A") (pintype "passive"))
      (node (ref "R17") (pin "S") (pinfunction "S_S") (pintype "passive"))
      (node (ref "R18") (pin "2") (pinfunction "2_2") (pintype "passive"))
    )
    (net (code "46") (name "Net-(IC5-OUT)") (class "Default")
      (node (ref "D4") (pin "C") (pinfunction "C_C") (pintype "passive"))
      (node (ref "IC5") (pin "2") (pinfunction "OUT_2") (pintype "output"))
      (node (ref "L3") (pin "1") (pinfunction "1_1") (pintype "passive"))
    )
    (net (code "47") (name "Net-(IC6-FB)") (class "Default")
      (node (ref "C27") (pin "2") (pinfunction "2_2") (pintype "passive"))
      (node (ref "IC6") (pin "4") (pinfunction "FB_4") (pintype "input"))
      (node (ref "R25") (pin "A") (pinfunction "A_A") (pintype "passive"))
      (node (ref "R25") (pin "S") (pinfunction "S_S") (pintype "passive"))
      (node (ref "R26") (pin "2") (pinfunction "2_2") (pintype "passive"))
    )
    (net (code "48") (name "Net-(IC6-OUT)") (class "Default")
      (node (ref "D5") (pin "C") (pinfunction "C_C") (pintype "passive"))
      (node (ref "IC6") (pin "2") (pinfunction "OUT_2") (pintype "output"))
      (node (ref "L4") (pin "1") (pinfunction "1_1") (pintype "passive"))
    )
    (net (code "49") (name "Net-(IC7-FB)") (class "Default")
      (node (ref "C31") (pin "2") (pinfunction "2_2") (pintype "passive"))
      (node (ref "IC7") (pin "4") (pinfunction "FB_4") (pintype "input"))
      (node (ref "R27") (pin "A") (pinfunction "A_A") (pintype "passive"))
      (node (ref "R27") (pin "S") (pinfunction "S_S") (pintype "passive"))
      (node (ref "R28") (pin "2") (pinfunction "2_2") (pintype "passive"))
    )
    (net (code "50") (name "Net-(IC7-OUT)") (class "Default")
      (node (ref "D6") (pin "C") (pinfunction "C_C") (pintype "passive"))
      (node (ref "IC7") (pin "2") (pinfunction "OUT_2") (pintype "output"))
      (node (ref "L5") (pin "1") (pinfunction "1_1") (pintype "passive"))
    )
    (net (code "51") (name "Net-(LED1-PadC)") (class "Default")
      (node (ref "LED1") (pin "C") (pinfunction "C_C") (pintype "passive"))
      (node (ref "R37") (pin "1") (pinfunction "1_1") (pintype "passive"))
    )
    (net (code "52") (name "Net-(PCB1-GPIO4)") (class "Default")
      (node (ref "PCB1") (pin "P$7") (pinfunction "GPIO4_P$7") (pintype "bidirectional"))
      (node (ref "R31") (pin "1") (pinfunction "1_1") (pintype "passive"))
    )
    (net (code "53") (name "Net-(Q1-B)") (class "Default")
      (node (ref "Q1") (pin "1") (pinfunction "B_1") (pintype "passive"))
      (node (ref "R29") (pin "1") (pinfunction "1_1") (pintype "passive"))
    )
    (net (code "54") (name "Net-(Q7-B)") (class "Default")
      (node (ref "Q7") (pin "1") (pinfunction "B_1") (pintype "passive"))
      (node (ref "R30") (pin "1") (pinfunction "1_1") (pintype "passive"))
    )
    (net (code "55") (name "Net-(U$2-SIGNAL)") (class "Default")
      (node (ref "U$2") (pin "P$3") (pinfunction "SIGNAL_P$3") (pintype "bidirectional"))
      (node (ref "U6") (pin "P$11") (pinfunction "EX_ANT_P$11") (pintype "bidirectional"))
    )
    (net (code "56") (name "Net-(U3-ADDR)") (class "Default")
      (node (ref "R14") (pin "1") (pinfunction "1_1") (pintype "passive"))
      (node (ref "U3") (pin "1") (pinfunction "ADDR_1") (pintype "bidirectional"))
    )
    (net (code "57") (name "Net-(U3-ALERT)") (class "Default")
      (node (ref "R9") (pin "2") (pinfunction "2_2") (pintype "passive"))
      (node (ref "U3") (pin "2") (pinfunction "ALERT_2") (pintype "bidirectional"))
    )
    (net (code "58") (name "Net-(U6-RX)") (class "Default")
      (node (ref "D9") (pin "A") (pinfunction "A_A") (pintype "passive"))
      (node (ref "R35") (pin "1") (pinfunction "1_1") (pintype "passive"))
      (node (ref "U6") (pin "P$10") (pinfunction "RX_P$10") (pintype "bidirectional"))
    )
    (net (code "59") (name "Net-(U7-OE)") (class "Default")
      (node (ref "R16") (pin "1") (pinfunction "1_1") (pintype "passive"))
      (node (ref "U7") (pin "10") (pinfunction "OE_10") (pintype "bidirectional"))
    )
    (net (code "60") (name "POWER_LED") (class "Default")
      (node (ref "R15") (pin "1") (pinfunction "1_1") (pintype "passive"))
      (node (ref "X1") (pin "P$5") (pinfunction "5_P$5") (pintype "passive"))
    )
    (net (code "61") (name "PT1_S+") (class "Default")
      (node (ref "U3") (pin "4") (pinfunction "AIN0_4") (pintype "bidirectional"))
      (node (ref "X4") (pin "P$2") (pinfunction "2_P$2") (pintype "passive"))
    )
    (net (code "62") (name "PT2_S+") (class "Default")
      (node (ref "U3") (pin "5") (pinfunction "AIN1_5") (pintype "bidirectional"))
      (node (ref "X4") (pin "P$5") (pinfunction "5_P$5") (pintype "passive"))
    )
    (net (code "63") (name "PT3_S+") (class "Default")
      (node (ref "U3") (pin "6") (pinfunction "AIN2_6") (pintype "bidirectional"))
      (node (ref "X4") (pin "P$8") (pinfunction "8_P$8") (pintype "passive"))
    )
    (net (code "64") (name "PT4_S+") (class "Default")
      (node (ref "U3") (pin "7") (pinfunction "AIN3_7") (pintype "bidirectional"))
      (node (ref "X4") (pin "P$11") (pinfunction "11_P$11") (pintype "passive"))
    )
    (net (code "65") (name "RPI_3.3V") (class "Default")
      (node (ref "C8") (pin "1") (pinfunction "1_1") (pintype "passive"))
      (node (ref "PCB1") (pin "P$1") (pinfunction "3V3_P$1") (pintype "bidirectional"))
      (node (ref "R16") (pin "2") (pinfunction "2_2") (pintype "passive"))
      (node (ref "U7") (pin "2") (pinfunction "VCCA_2") (pintype "bidirectional"))
    )
    (net (code "66") (name "RPI_DROGE2_S+") (class "Default")
      (node (ref "R29") (pin "2") (pinfunction "2_2") (pintype "passive"))
    )
    (net (code "67") (name "RPI_DROUGE1") (class "Default")
      (node (ref "U$11") (pin "COM") (pinfunction "COM_COM") (pintype "bidirectional"))
      (node (ref "X4") (pin "P$13") (pinfunction "13_P$13") (pintype "passive"))
      (node (ref "X4") (pin "P$21") (pinfunction "21_P$21") (pintype "passive"))
    )
    (net (code "68") (name "RPI_DROUGE1_S+") (class "Default")
      (node (ref "PCB1") (pin "P$16") (pinfunction "GPIO23_P$16") (pintype "bidirectional"))
      (node (ref "R30") (pin "2") (pinfunction "2_2") (pintype "passive"))
    )
    (net (code "69") (name "RPI_DROUGE2") (class "Default")
      (node (ref "U$13") (pin "COM") (pinfunction "COM_COM") (pintype "bidirectional"))
      (node (ref "X4") (pin "P$15") (pinfunction "15_P$15") (pintype "passive"))
      (node (ref "X4") (pin "P$23") (pinfunction "23_P$23") (pintype "passive"))
    )
    (net (code "70") (name "RPI_DROUGE2_S+") (class "Default")
      (node (ref "PCB1") (pin "P$18") (pinfunction "GPIO24_P$18") (pintype "bidirectional"))
    )
    (net (code "71") (name "RPI_RX") (class "Default")
      (node (ref "PCB1") (pin "P$10") (pinfunction "GPIO15_P$10") (pintype "bidirectional"))
      (node (ref "U6") (pin "P$9") (pinfunction "TX_P$9") (pintype "bidirectional"))
    )
    (net (code "72") (name "RPI_SCL_3.3V") (class "Default")
      (node (ref "IC3") (pin "2") (pinfunction "SCL/SPC_2") (pintype "bidirectional"))
      (node (ref "IC4") (pin "P$8") (pinfunction "SCL_P$8") (pintype "bidirectional"))
      (node (ref "PCB1") (pin "P$5") (pinfunction "GPIO3_P$5") (pintype "bidirectional"))
      (node (ref "R6") (pin "2") (pinfunction "2_2") (pintype "passive"))
      (node (ref "R8") (pin "1") (pinfunction "1_1") (pintype "passive"))
      (node (ref "U3") (pin "10") (pinfunction "SCL_10") (pintype "bidirectional"))
    )
    (net (code "73") (name "RPI_SDA_3.3V") (class "Default")
      (node (ref "IC3") (pin "4") (pinfunction "SDA/SDI/SDO_4") (pintype "bidirectional"))
      (node (ref "IC4") (pin "P$7") (pinfunction "SDA_P$7") (pintype "bidirectional"))
      (node (ref "PCB1") (pin "P$3") (pinfunction "GPIO2_P$3") (pintype "bidirectional"))
      (node (ref "R5") (pin "2") (pinfunction "2_2") (pintype "passive"))
      (node (ref "R7") (pin "2") (pinfunction "2_2") (pintype "passive"))
      (node (ref "U3") (pin "9") (pinfunction "SDA_9") (pintype "bidirectional"))
    )
    (net (code "74") (name "RPI_TX") (class "Default")
      (node (ref "D9") (pin "C") (pinfunction "C_C") (pintype "passive"))
      (node (ref "PCB1") (pin "P$8") (pinfunction "GPIO14_P$8") (pintype "bidirectional"))
    )
    (net (code "75") (name "SERVO1_S+_3.3V") (class "Default")
      (node (ref "PCB1") (pin "P$12") (pinfunction "GPIO18_P$12") (pintype "bidirectional"))
      (node (ref "U7") (pin "1") (pinfunction "A1_1") (pintype "bidirectional"))
    )
    (net (code "76") (name "SERVO1_S+_5V") (class "Default")
      (node (ref "U7") (pin "20") (pinfunction "B1_20") (pintype "bidirectional"))
      (node (ref "X1") (pin "P$7") (pinfunction "7_P$7") (pintype "passive"))
    )
    (net (code "77") (name "SERVO2_S+_3.3V") (class "Default")
      (node (ref "PCB1") (pin "P$33") (pinfunction "GPIO13_P$33") (pintype "bidirectional"))
      (node (ref "U7") (pin "3") (pinfunction "A2_3") (pintype "bidirectional"))
    )
    (net (code "78") (name "SERVO2_S+_5V") (class "Default")
      (node (ref "U7") (pin "18") (pinfunction "B2_18") (pintype "bidirectional"))
      (node (ref "X1") (pin "P$10") (pinfunction "10_P$10") (pintype "passive"))
    )
    (net (code "79") (name "SERVO3_S+_3.3V") (class "Default")
      (node (ref "PCB1") (pin "P$32") (pinfunction "GPIO12_P$32") (pintype "bidirectional"))
      (node (ref "U7") (pin "4") (pinfunction "A3_4") (pintype "bidirectional"))
    )
    (net (code "80") (name "SERVO3_S+_5V") (class "Default")
      (node (ref "U7") (pin "17") (pinfunction "B3_17") (pintype "bidirectional"))
      (node (ref "X1") (pin "P$13") (pinfunction "13_P$13") (pintype "passive"))
    )
    (net (code "81") (name "SERVO4_S+_3.3V") (class "Default")
      (node (ref "PCB1") (pin "P$35") (pinfunction "GPIO19_P$35") (pintype "bidirectional"))
      (node (ref "U7") (pin "5") (pinfunction "A4_5") (pintype "bidirectional"))
    )
    (net (code "82") (name "SERVO4_S+_5V") (class "Default")
      (node (ref "U7") (pin "16") (pinfunction "B4_16") (pintype "bidirectional"))
      (node (ref "X1") (pin "P$16") (pinfunction "16_P$16") (pintype "passive"))
    )
    (net (code "83") (name "SW_MODE_SUPPLY1") (class "Default")
      (node (ref "C19") (pin "1") (pinfunction "1_1") (pintype "passive"))
      (node (ref "C7") (pin "+") (pinfunction "+_+") (pintype "passive"))
      (node (ref "L2") (pin "2") (pinfunction "2_2") (pintype "passive"))
      (node (ref "R1") (pin "E") (pinfunction "E_E") (pintype "passive"))
      (node (ref "X1") (pin "P$8") (pinfunction "8_P$8") (pintype "passive"))
      (node (ref "X4") (pin "P$1") (pinfunction "1_P$1") (pintype "passive"))
      (node (ref "X4") (pin "P$10") (pinfunction "10_P$10") (pintype "passive"))
      (node (ref "X4") (pin "P$4") (pinfunction "4_P$4") (pintype "passive"))
      (node (ref "X4") (pin "P$7") (pinfunction "7_P$7") (pintype "passive"))
    )
    (net (code "84") (name "SW_MODE_SUPPLY2") (class "Default")
      (node (ref "C21") (pin "+") (pinfunction "+_+") (pintype "passive"))
      (node (ref "C23") (pin "1") (pinfunction "1_1") (pintype "passive"))
      (node (ref "L3") (pin "2") (pinfunction "2_2") (pintype "passive"))
      (node (ref "R17") (pin "E") (pinfunction "E_E") (pintype "passive"))
      (node (ref "X1") (pin "P$11") (pinfunction "11_P$11") (pintype "passive"))
    )
    (net (code "85") (name "SW_MODE_SUPPLY3") (class "Default")
      (node (ref "C25") (pin "+") (pinfunction "+_+") (pintype "passive"))
      (node (ref "C27") (pin "1") (pinfunction "1_1") (pintype "passive"))
      (node (ref "L4") (pin "2") (pinfunction "2_2") (pintype "passive"))
      (node (ref "R25") (pin "E") (pinfunction "E_E") (pintype "passive"))
      (node (ref "X1") (pin "P$14") (pinfunction "14_P$14") (pintype "passive"))
    )
    (net (code "86") (name "SW_MODE_SUPPLY4") (class "Default")
      (node (ref "C29") (pin "+") (pinfunction "+_+") (pintype "passive"))
      (node (ref "C31") (pin "1") (pinfunction "1_1") (pintype "passive"))
      (node (ref "L5") (pin "2") (pinfunction "2_2") (pintype "passive"))
      (node (ref "R27") (pin "E") (pinfunction "E_E") (pintype "passive"))
      (node (ref "X1") (pin "P$17") (pinfunction "17_P$17") (pintype "passive"))
    )
    (net (code "87") (name "X_CHANNEL") (class "Default")
      (node (ref "R12") (pin "1") (pinfunction "1_1") (pintype "passive"))
      (node (ref "X1") (pin "P$22") (pinfunction "22_P$22") (pintype "passive"))
    )
    (net (code "88") (name "X_CHANNEL_3V3") (class "Default")
      (node (ref "PCB1") (pin "P$15") (pinfunction "GPIO22_P$15") (pintype "bidirectional"))
      (node (ref "R12") (pin "2") (pinfunction "2_2") (pintype "passive"))
      (node (ref "R13") (pin "1") (pinfunction "1_1") (pintype "passive"))
    )
    (net (code "89") (name "unconnected-(IC4-INT1-PadP$6)") (class "Default")
      (node (ref "IC4") (pin "P$6") (pinfunction "INT1_P$6") (pintype "output"))
    )
    (net (code "90") (name "unconnected-(IC4-INT2-PadP$5)") (class "Default")
      (node (ref "IC4") (pin "P$5") (pinfunction "INT2_P$5") (pintype "output"))
    )
    (net (code "91") (name "unconnected-(PCB1-3V3-PadP$17)") (class "Default")
      (node (ref "PCB1") (pin "P$17") (pinfunction "3V3_P$17") (pintype "bidirectional"))
    )
    (net (code "92") (name "unconnected-(PCB1-GPIO5-PadP$29)") (class "Default")
      (node (ref "PCB1") (pin "P$29") (pinfunction "GPIO5_P$29") (pintype "bidirectional"))
    )
    (net (code "93") (name "unconnected-(PCB1-GPIO6-PadP$31)") (class "Default")
      (node (ref "PCB1") (pin "P$31") (pinfunction "GPIO6_P$31") (pintype "bidirectional"))
    )
    (net (code "94") (name "unconnected-(PCB1-GPIO7-PadP$26)") (class "Default")
      (node (ref "PCB1") (pin "P$26") (pinfunction "GPIO7_P$26") (pintype "bidirectional"))
    )
    (net (code "95") (name "unconnected-(PCB1-GPIO8-PadP$24)") (class "Default")
      (node (ref "PCB1") (pin "P$24") (pinfunction "GPIO8_P$24") (pintype "bidirectional"))
    )
    (net (code "96") (name "unconnected-(PCB1-GPIO9-PadP$21)") (class "Default")
      (node (ref "PCB1") (pin "P$21") (pinfunction "GPIO9_P$21") (pintype "bidirectional"))
    )
    (net (code "97") (name "unconnected-(PCB1-GPIO10-PadP$19)") (class "Default")
      (node (ref "PCB1") (pin "P$19") (pinfunction "GPIO10_P$19") (pintype "bidirectional"))
    )
    (net (code "98") (name "unconnected-(PCB1-GPIO11-PadP$23)") (class "Default")
      (node (ref "PCB1") (pin "P$23") (pinfunction "GPIO11_P$23") (pintype "bidirectional"))
    )
    (net (code "99") (name "unconnected-(PCB1-GPIO16-PadP$36)") (class "Default")
      (node (ref "PCB1") (pin "P$36") (pinfunction "GPIO16_P$36") (pintype "bidirectional"))
    )
    (net (code "100") (name "unconnected-(PCB1-GPIO20-PadP$38)") (class "Default")
      (node (ref "PCB1") (pin "P$38") (pinfunction "GPIO20_P$38") (pintype "bidirectional"))
    )
    (net (code "101") (name "unconnected-(PCB1-GPIO21-PadP$40)") (class "Default")
      (node (ref "PCB1") (pin "P$40") (pinfunction "GPIO21_P$40") (pintype "bidirectional"))
    )
    (net (code "102") (name "unconnected-(PCB1-GPIO25-PadP$22)") (class "Default")
      (node (ref "PCB1") (pin "P$22") (pinfunction "GPIO25_P$22") (pintype "bidirectional"))
    )
    (net (code "103") (name "unconnected-(PCB1-GPIO26-PadP$37)") (class "Default")
      (node (ref "PCB1") (pin "P$37") (pinfunction "GPIO26_P$37") (pintype "bidirectional"))
    )
    (net (code "104") (name "unconnected-(PCB1-ID_SC*-PadP$28)") (class "Default")
      (node (ref "PCB1") (pin "P$28") (pinfunction "ID_SC*_P$28") (pintype "bidirectional"))
    )
    (net (code "105") (name "unconnected-(PCB1-ID_SD*-PadP$27)") (class "Default")
      (node (ref "PCB1") (pin "P$27") (pinfunction "ID_SD*_P$27") (pintype "bidirectional"))
    )
    (net (code "106") (name "unconnected-(U$11-PadNC)") (class "Default")
      (node (ref "U$11") (pin "NC") (pinfunction "NC_NC") (pintype "bidirectional"))
    )
    (net (code "107") (name "unconnected-(U$13-PadNC)") (class "Default")
      (node (ref "U$13") (pin "NC") (pinfunction "NC_NC") (pintype "bidirectional"))
    )
    (net (code "108") (name "unconnected-(U4-P4-Pad4)") (class "Default")
      (node (ref "U4") (pin "4") (pinfunction "P4_4") (pintype "bidirectional"))
    )
    (net (code "109") (name "unconnected-(U5-P4-Pad4)") (class "Default")
      (node (ref "U5") (pin "4") (pinfunction "P4_4") (pintype "bidirectional"))
    )
    (net (code "110") (name "unconnected-(U6-NC-PadP$6)") (class "Default")
      (node (ref "U6") (pin "P$6") (pinfunction "NC_P$6") (pintype "bidirectional"))
    )
    (net (code "111") (name "unconnected-(U6-NC-PadP$7)") (class "Default")
      (node (ref "U6") (pin "P$7") (pinfunction "NC_P$7") (pintype "bidirectional"))
    )
    (net (code "112") (name "unconnected-(U6-NC-PadP$15)") (class "Default")
      (node (ref "U6") (pin "P$15") (pinfunction "NC_P$15") (pintype "bidirectional"))
    )
    (net (code "113") (name "unconnected-(U6-NC-PadP$16)") (class "Default")
      (node (ref "U6") (pin "P$16") (pinfunction "NC_P$16") (pintype "bidirectional"))
    )
    (net (code "114") (name "unconnected-(U6-NC-PadP$17)") (class "Default")
      (node (ref "U6") (pin "P$17") (pinfunction "NC_P$17") (pintype "bidirectional"))
    )
    (net (code "115") (name "unconnected-(U6-NC-PadP$18)") (class "Default")
      (node (ref "U6") (pin "P$18") (pinfunction "NC_P$18") (pintype "bidirectional"))
    )
    (net (code "116") (name "unconnected-(U6-NC-PadP$20)") (class "Default")
      (node (ref "U6") (pin "P$20") (pinfunction "NC_P$20") (pintype "bidirectional"))
    )
    (net (code "117") (name "unconnected-(U6-NRESET-PadP$2)") (class "Default")
      (node (ref "U6") (pin "P$2") (pinfunction "NRESET_P$2") (pintype "bidirectional"))
    )
    (net (code "118") (name "unconnected-(U6-RTCM-PadP$14)") (class "Default")
      (node (ref "U6") (pin "P$14") (pinfunction "RTCM_P$14") (pintype "bidirectional"))
    )
    (net (code "119") (name "unconnected-(U7-A5-Pad6)") (class "Default")
      (node (ref "U7") (pin "6") (pinfunction "A5_6") (pintype "bidirectional"))
    )
    (net (code "120") (name "unconnected-(U7-A6-Pad7)") (class "Default")
      (node (ref "U7") (pin "7") (pinfunction "A6_7") (pintype "bidirectional"))
    )
    (net (code "121") (name "unconnected-(U7-A7-Pad8)") (class "Default")
      (node (ref "U7") (pin "8") (pinfunction "A7_8") (pintype "bidirectional"))
    )
    (net (code "122") (name "unconnected-(U7-A8-Pad9)") (class "Default")
      (node (ref "U7") (pin "9") (pinfunction "A8_9") (pintype "bidirectional"))
    )
    (net (code "123") (name "unconnected-(U7-B5-Pad15)") (class "Default")
      (node (ref "U7") (pin "15") (pinfunction "B5_15") (pintype "bidirectional"))
    )
    (net (code "124") (name "unconnected-(U7-B6-Pad14)") (class "Default")
      (node (ref "U7") (pin "14") (pinfunction "B6_14") (pintype "bidirectional"))
    )
    (net (code "125") (name "unconnected-(U7-B7-Pad13)") (class "Default")
      (node (ref "U7") (pin "13") (pinfunction "B7_13") (pintype "bidirectional"))
    )
    (net (code "126") (name "unconnected-(U7-B8-Pad12)") (class "Default")
      (node (ref "U7") (pin "12") (pinfunction "B8_12") (pintype "bidirectional"))
    )
    (net (code "127") (name "unconnected-(U8-P4-Pad4)") (class "Default")
      (node (ref "U8") (pin "4") (pinfunction "P4_4") (pintype "bidirectional"))
    )
  )
)
